# POWER_EFUSE.net
KiCad netlist of a schematic drawn in Altium Designer
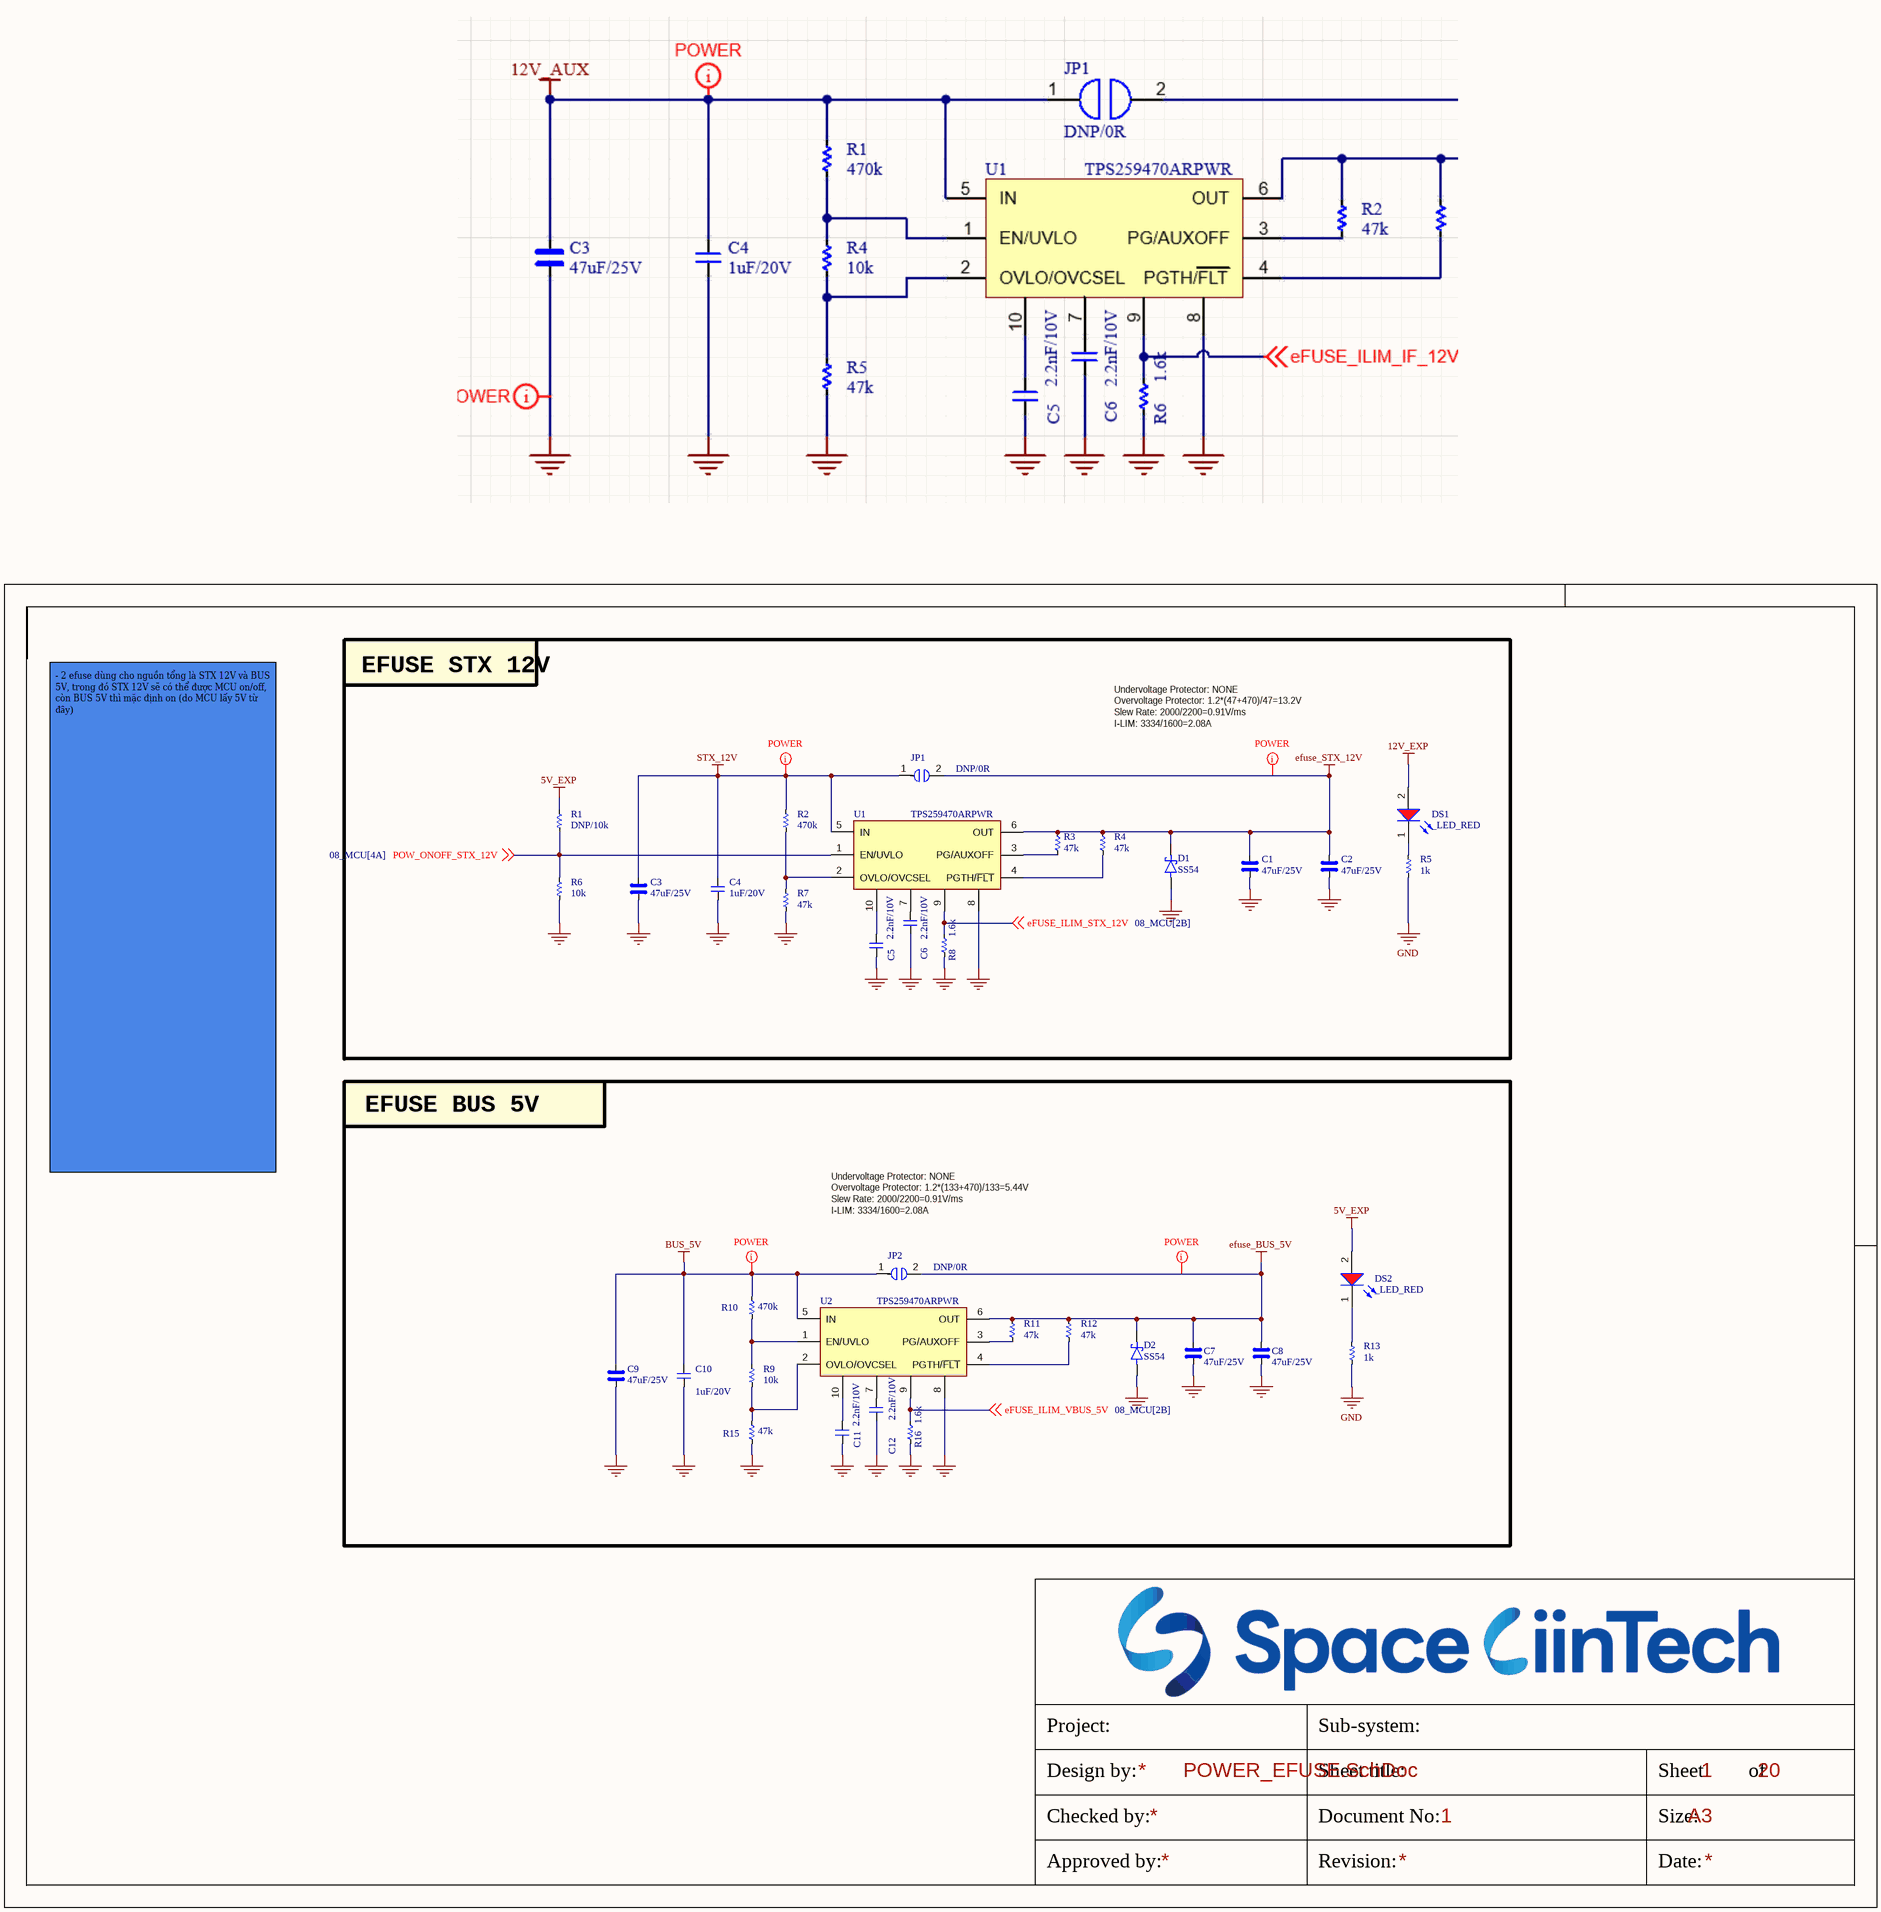
[diagram p0: POWER_EFUSE.SchDoc]

(export (version "E")
  (design (tool "Eeschema 10.0.6"))
  (components
    (comp (ref "C1")
      (value "47uF/25V")
      (footprint "CAP_C_3225X80")
      (description "CAP High Value")
      (libsource (lib "LABLIB") (part "_CAP_C_High_2"))
    )
    (comp (ref "C2")
      (value "47uF/25V")
      (footprint "CAP_C_3225X80")
      (description "CAP High Value")
      (libsource (lib "LABLIB") (part "_CAP_C_High_2"))
    )
    (comp (ref "C3")
      (value "47uF/25V")
      (footprint "CAP_C_3225X80")
      (description "CAP High Value")
      (libsource (lib "LABLIB") (part "_CAP_C_High_2"))
    )
    (comp (ref "C4")
      (value "1uF/20V")
      (footprint "CAP_C_1005X50_L")
      (description "CAP")
      (libsource (lib "LABLIB") (part "_CAP_C_2"))
    )
    (comp (ref "C5")
      (value "2.2nF/10V")
      (footprint "CAP_C_1005X50_L")
      (description "CAP")
      (libsource (lib "LABLIB") (part "_CAP_C_2"))
    )
    (comp (ref "C6")
      (value "2.2nF/10V")
      (footprint "CAP_C_1005X50_L")
      (description "CAP")
      (libsource (lib "LABLIB") (part "_CAP_C_2"))
    )
    (comp (ref "C7")
      (value "47uF/25V")
      (footprint "CAP_C_3225X80")
      (description "CAP High Value")
      (libsource (lib "LABLIB") (part "_CAP_C_High_2"))
    )
    (comp (ref "C8")
      (value "47uF/25V")
      (footprint "CAP_C_3225X80")
      (description "CAP High Value")
      (libsource (lib "LABLIB") (part "_CAP_C_High_2"))
    )
    (comp (ref "C9")
      (value "47uF/25V")
      (footprint "CAP_C_3225X80")
      (description "CAP High Value")
      (libsource (lib "LABLIB") (part "_CAP_C_High_2"))
    )
    (comp (ref "C10")
      (value "1uF/20V")
      (footprint "CAP_C_1005X50_L")
      (description "CAP")
      (libsource (lib "LABLIB") (part "_CAP_C_2"))
    )
    (comp (ref "C11")
      (value "2.2nF/10V")
      (footprint "CAP_C_1005X50_L")
      (description "CAP")
      (libsource (lib "LABLIB") (part "_CAP_C_2"))
    )
    (comp (ref "C12")
      (value "2.2nF/10V")
      (footprint "CAP_C_1005X50_L")
      (description "CAP")
      (libsource (lib "LABLIB") (part "_CAP_C_2"))
    )
    (comp (ref "D1")
      (value "SS54")
      (footprint "DO-214AC_SMA")
      (description "DIODE SCHOTTKY")
      (libsource (lib "LABLIB") (part "DIODE SCHOTTKY"))
    )
    (comp (ref "D2")
      (value "SS54")
      (footprint "DO-214AC_SMA")
      (description "DIODE SCHOTTKY")
      (libsource (lib "LABLIB") (part "DIODE SCHOTTKY"))
    )
    (comp (ref "DS1") (value "_LED_RED") (footprint "LED_0603") (libsource (lib "LABLIB") (part "_LED_RED")))
    (comp (ref "DS2") (value "_LED_RED") (footprint "LED_0603") (libsource (lib "LABLIB") (part "_LED_RED")))
    (comp (ref "JP1")
      (value "DNP/0R")
      (footprint "JUMPER_1608")
      (libsource (lib "BEE-DAL_EXP_sche") (part "JUMPER_1_1"))
    )
    (comp (ref "JP2")
      (value "DNP/0R")
      (footprint "JUMPER_1608")
      (libsource (lib "BEE-DAL_EXP_sche") (part "JUMPER_1_1"))
    )
    (comp (ref "R1")
      (value "DNP/10k")
      (footprint "RES_C_1005X40")
      (description "RES")
      (libsource (lib "LABLIB") (part "_RES_B_2"))
    )
    (comp (ref "R2")
      (value "470k")
      (footprint "RES_C_1005X40")
      (description "RES")
      (libsource (lib "LABLIB") (part "_RES_B_2"))
    )
    (comp (ref "R3")
      (value "47k")
      (footprint "RES_C_1005X40")
      (description "RES")
      (libsource (lib "LABLIB") (part "_RES_B_2"))
    )
    (comp (ref "R4")
      (value "47k")
      (footprint "RES_C_1005X40")
      (description "RES")
      (libsource (lib "LABLIB") (part "_RES_B_2"))
    )
    (comp (ref "R5")
      (value "1k")
      (footprint "RES_C_1005X40")
      (description "RES")
      (libsource (lib "LABLIB") (part "_RES_B_2"))
    )
    (comp (ref "R6")
      (value "10k")
      (footprint "RES_C_1005X40")
      (description "RES")
      (libsource (lib "LABLIB") (part "_RES_B_2"))
    )
    (comp (ref "R7")
      (value "47k")
      (footprint "RES_C_1005X40")
      (description "RES")
      (libsource (lib "LABLIB") (part "_RES_B_2"))
    )
    (comp (ref "R8")
      (value "1.6k")
      (footprint "RES_C_1005X40")
      (description "RES")
      (libsource (lib "LABLIB") (part "_RES_B_2"))
    )
    (comp (ref "R9")
      (value "10k")
      (footprint "RES_C_1005X40")
      (description "RES")
      (libsource (lib "LABLIB") (part "_RES_B_2"))
    )
    (comp (ref "R10")
      (value "470k")
      (footprint "RES_C_1005X40")
      (description "RES")
      (libsource (lib "LABLIB") (part "_RES_B_2"))
    )
    (comp (ref "R11")
      (value "47k")
      (footprint "RES_C_1005X40")
      (description "RES")
      (libsource (lib "LABLIB") (part "_RES_B_2"))
    )
    (comp (ref "R12")
      (value "47k")
      (footprint "RES_C_1005X40")
      (description "RES")
      (libsource (lib "LABLIB") (part "_RES_B_2"))
    )
    (comp (ref "R13")
      (value "1k")
      (footprint "RES_C_1005X40")
      (description "RES")
      (libsource (lib "LABLIB") (part "_RES_B_2"))
    )
    (comp (ref "R15")
      (value "47k")
      (footprint "RES_C_1005X40")
      (description "RES")
      (libsource (lib "LABLIB") (part "_RES_B_2"))
    )
    (comp (ref "R16")
      (value "1.6k")
      (footprint "RES_C_1005X40")
      (description "RES")
      (libsource (lib "LABLIB") (part "_RES_B_2"))
    )
    (comp (ref "U1")
      (value "TPS259470ARPWR")
      (footprint "VQFN-HR-10")
      (libsource (lib "BEE-DAL_EXP_sche") (part "TPS259470ARPWR"))
    )
    (comp (ref "U2")
      (value "TPS259470ARPWR")
      (footprint "VQFN-HR-10")
      (libsource (lib "BEE-DAL_EXP_sche") (part "TPS259470ARPWR"))
    )
  )
  (nets
    (net (code "1") (name "5V_EXP") (class "Default")
      (node (ref "DS2") (pin "2") (pinfunction "A_2") (pintype "passive"))
      (node (ref "R1") (pin "1") (pinfunction "1_1") (pintype "passive"))
    )
    (net (code "2") (name "12V_EXP") (class "Default")
      (node (ref "DS1") (pin "2") (pinfunction "A_2") (pintype "passive"))
    )
    (net (code "3") (name "BUS_5V") (class "Default")
      (node (ref "C10") (pin "2") (pinfunction "2_2") (pintype "passive"))
      (node (ref "C9") (pin "2") (pinfunction "2_2") (pintype "passive"))
      (node (ref "JP2") (pin "1") (pinfunction "1_1") (pintype "passive"))
      (node (ref "R10") (pin "2") (pinfunction "2_2") (pintype "passive"))
      (node (ref "U2") (pin "5") (pinfunction "IN_5") (pintype "passive"))
    )
    (net (code "4") (name "GND") (class "Default")
      (node (ref "C1") (pin "1") (pinfunction "1_1") (pintype "passive"))
      (node (ref "C10") (pin "1") (pinfunction "1_1") (pintype "passive"))
      (node (ref "C11") (pin "1") (pinfunction "1_1") (pintype "passive"))
      (node (ref "C12") (pin "1") (pinfunction "1_1") (pintype "passive"))
      (node (ref "C2") (pin "1") (pinfunction "1_1") (pintype "passive"))
      (node (ref "C3") (pin "1") (pinfunction "1_1") (pintype "passive"))
      (node (ref "C4") (pin "1") (pinfunction "1_1") (pintype "passive"))
      (node (ref "C5") (pin "1") (pinfunction "1_1") (pintype "passive"))
      (node (ref "C6") (pin "1") (pinfunction "1_1") (pintype "passive"))
      (node (ref "C7") (pin "1") (pinfunction "1_1") (pintype "passive"))
      (node (ref "C8") (pin "1") (pinfunction "1_1") (pintype "passive"))
      (node (ref "C9") (pin "1") (pinfunction "1_1") (pintype "passive"))
      (node (ref "D1") (pin "2") (pinfunction "A_2") (pintype "passive"))
      (node (ref "D2") (pin "2") (pinfunction "A_2") (pintype "passive"))
      (node (ref "R13") (pin "1") (pinfunction "1_1") (pintype "passive"))
      (node (ref "R15") (pin "1") (pinfunction "1_1") (pintype "passive"))
      (node (ref "R16") (pin "1") (pinfunction "1_1") (pintype "passive"))
      (node (ref "R5") (pin "1") (pinfunction "1_1") (pintype "passive"))
      (node (ref "R6") (pin "2") (pinfunction "2_2") (pintype "passive"))
      (node (ref "R7") (pin "1") (pinfunction "1_1") (pintype "passive"))
      (node (ref "R8") (pin "1") (pinfunction "1_1") (pintype "passive"))
      (node (ref "U1") (pin "8") (pinfunction "8_8") (pintype "passive"))
      (node (ref "U2") (pin "8") (pinfunction "8_8") (pintype "passive"))
    )
    (net (code "5") (name "Net-(C5-Pad2)") (class "Default")
      (node (ref "C5") (pin "2") (pinfunction "2_2") (pintype "passive"))
      (node (ref "U1") (pin "10") (pinfunction "10_10") (pintype "passive"))
    )
    (net (code "6") (name "Net-(C6-Pad2)") (class "Default")
      (node (ref "C6") (pin "2") (pinfunction "2_2") (pintype "passive"))
      (node (ref "U1") (pin "7") (pinfunction "7_7") (pintype "passive"))
    )
    (net (code "7") (name "Net-(C11-Pad2)") (class "Default")
      (node (ref "C11") (pin "2") (pinfunction "2_2") (pintype "passive"))
      (node (ref "U2") (pin "10") (pinfunction "10_10") (pintype "passive"))
    )
    (net (code "8") (name "Net-(C12-Pad2)") (class "Default")
      (node (ref "C12") (pin "2") (pinfunction "2_2") (pintype "passive"))
      (node (ref "U2") (pin "7") (pinfunction "7_7") (pintype "passive"))
    )
    (net (code "9") (name "Net-(DS1-K)") (class "Default")
      (node (ref "DS1") (pin "1") (pinfunction "K_1") (pintype "passive"))
      (node (ref "R5") (pin "2") (pinfunction "2_2") (pintype "passive"))
    )
    (net (code "10") (name "Net-(DS2-K)") (class "Default")
      (node (ref "DS2") (pin "1") (pinfunction "K_1") (pintype "passive"))
      (node (ref "R13") (pin "2") (pinfunction "2_2") (pintype "passive"))
    )
    (net (code "11") (name "Net-(U1-OVLO{slash}OVCSEL)") (class "Default")
      (node (ref "R2") (pin "1") (pinfunction "1_1") (pintype "passive"))
      (node (ref "R7") (pin "2") (pinfunction "2_2") (pintype "passive"))
      (node (ref "U1") (pin "2") (pinfunction "OVLO/OVCSEL_2") (pintype "passive"))
    )
    (net (code "12") (name "Net-(U1-PGTH{slash}~{FLT})") (class "Default")
      (node (ref "R4") (pin "1") (pinfunction "1_1") (pintype "passive"))
      (node (ref "U1") (pin "4") (pinfunction "PGTH/~{FLT}_4") (pintype "passive"))
    )
    (net (code "13") (name "Net-(U1-PG{slash}AUXOFF)") (class "Default")
      (node (ref "R3") (pin "1") (pinfunction "1_1") (pintype "passive"))
      (node (ref "U1") (pin "3") (pinfunction "PG/AUXOFF_3") (pintype "passive"))
    )
    (net (code "14") (name "Net-(U2-EN{slash}UVLO)") (class "Default")
      (node (ref "R10") (pin "1") (pinfunction "1_1") (pintype "passive"))
      (node (ref "R9") (pin "2") (pinfunction "2_2") (pintype "passive"))
      (node (ref "U2") (pin "1") (pinfunction "EN/UVLO_1") (pintype "passive"))
    )
    (net (code "15") (name "Net-(U2-OVLO{slash}OVCSEL)") (class "Default")
      (node (ref "R15") (pin "2") (pinfunction "2_2") (pintype "passive"))
      (node (ref "R9") (pin "1") (pinfunction "1_1") (pintype "passive"))
      (node (ref "U2") (pin "2") (pinfunction "OVLO/OVCSEL_2") (pintype "passive"))
    )
    (net (code "16") (name "Net-(U2-PGTH{slash}~{FLT})") (class "Default")
      (node (ref "R12") (pin "1") (pinfunction "1_1") (pintype "passive"))
      (node (ref "U2") (pin "4") (pinfunction "PGTH/~{FLT}_4") (pintype "passive"))
    )
    (net (code "17") (name "Net-(U2-PG{slash}AUXOFF)") (class "Default")
      (node (ref "R11") (pin "1") (pinfunction "1_1") (pintype "passive"))
      (node (ref "U2") (pin "3") (pinfunction "PG/AUXOFF_3") (pintype "passive"))
    )
    (net (code "18") (name "POW_ONOFF_STX_12V") (class "Default")
      (node (ref "R1") (pin "2") (pinfunction "2_2") (pintype "passive"))
      (node (ref "R6") (pin "1") (pinfunction "1_1") (pintype "passive"))
      (node (ref "U1") (pin "1") (pinfunction "EN/UVLO_1") (pintype "passive"))
    )
    (net (code "19") (name "STX_12V") (class "Default")
      (node (ref "C3") (pin "2") (pinfunction "2_2") (pintype "passive"))
      (node (ref "C4") (pin "2") (pinfunction "2_2") (pintype "passive"))
      (node (ref "JP1") (pin "1") (pinfunction "1_1") (pintype "passive"))
      (node (ref "R2") (pin "2") (pinfunction "2_2") (pintype "passive"))
      (node (ref "U1") (pin "5") (pinfunction "IN_5") (pintype "passive"))
    )
    (net (code "20") (name "eFUSE_ILIM_STX_12V") (class "Default")
      (node (ref "R8") (pin "2") (pinfunction "2_2") (pintype "passive"))
      (node (ref "U1") (pin "9") (pinfunction "9_9") (pintype "passive"))
    )
    (net (code "21") (name "eFUSE_ILIM_VBUS_5V") (class "Default")
      (node (ref "R16") (pin "2") (pinfunction "2_2") (pintype "passive"))
      (node (ref "U2") (pin "9") (pinfunction "9_9") (pintype "passive"))
    )
    (net (code "22") (name "efuse_BUS_5V") (class "Default")
      (node (ref "C7") (pin "2") (pinfunction "2_2") (pintype "passive"))
      (node (ref "C8") (pin "2") (pinfunction "2_2") (pintype "passive"))
      (node (ref "D2") (pin "1") (pinfunction "K_1") (pintype "passive"))
      (node (ref "JP2") (pin "2") (pinfunction "2_2") (pintype "passive"))
      (node (ref "R11") (pin "2") (pinfunction "2_2") (pintype "passive"))
      (node (ref "R12") (pin "2") (pinfunction "2_2") (pintype "passive"))
      (node (ref "U2") (pin "6") (pinfunction "OUT_6") (pintype "passive"))
    )
    (net (code "23") (name "efuse_STX_12V") (class "Default")
      (node (ref "C1") (pin "2") (pinfunction "2_2") (pintype "passive"))
      (node (ref "C2") (pin "2") (pinfunction "2_2") (pintype "passive"))
      (node (ref "D1") (pin "1") (pinfunction "K_1") (pintype "passive"))
      (node (ref "JP1") (pin "2") (pinfunction "2_2") (pintype "passive"))
      (node (ref "R3") (pin "2") (pinfunction "2_2") (pintype "passive"))
      (node (ref "R4") (pin "2") (pinfunction "2_2") (pintype "passive"))
      (node (ref "U1") (pin "6") (pinfunction "OUT_6") (pintype "passive"))
    )
  )
)
